# baseboard_v1.net
KiCad netlist of a schematic drawn in EAGLE
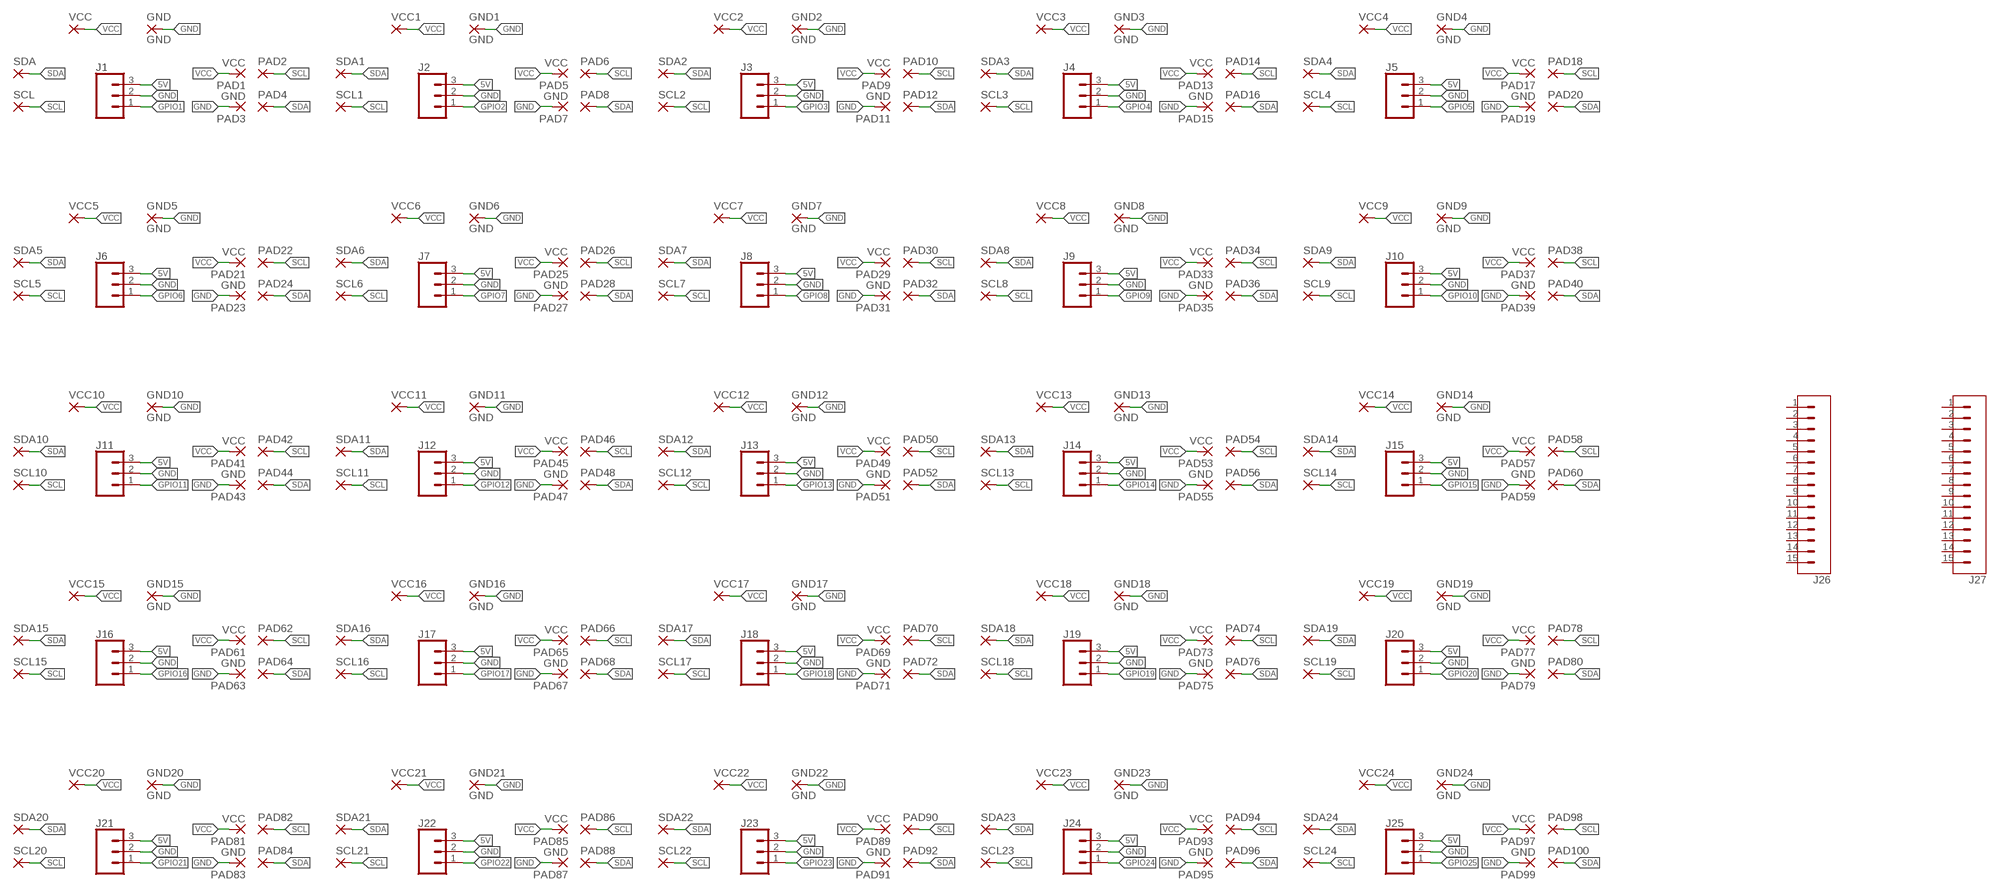
[diagram p0: schematic, sheet 1]

(export (version "E")
  (design (tool "Eeschema 10.0.6"))
  (components
    (comp (ref "GND")
      (value "GND")
      (footprint "eagle-import:2,15_1,0")
      (libsource (lib "eagle-import") (part "2,15/1,0"))
    )
    (comp (ref "GND1")
      (value "GND")
      (footprint "eagle-import:2,15_1,0")
      (libsource (lib "eagle-import") (part "2,15/1,0"))
    )
    (comp (ref "GND2")
      (value "GND")
      (footprint "eagle-import:2,15_1,0")
      (libsource (lib "eagle-import") (part "2,15/1,0"))
    )
    (comp (ref "GND3")
      (value "GND")
      (footprint "eagle-import:2,15_1,0")
      (libsource (lib "eagle-import") (part "2,15/1,0"))
    )
    (comp (ref "GND4")
      (value "GND")
      (footprint "eagle-import:2,15_1,0")
      (libsource (lib "eagle-import") (part "2,15/1,0"))
    )
    (comp (ref "GND5")
      (value "GND")
      (footprint "eagle-import:2,15_1,0")
      (libsource (lib "eagle-import") (part "2,15/1,0"))
    )
    (comp (ref "GND6")
      (value "GND")
      (footprint "eagle-import:2,15_1,0")
      (libsource (lib "eagle-import") (part "2,15/1,0"))
    )
    (comp (ref "GND7")
      (value "GND")
      (footprint "eagle-import:2,15_1,0")
      (libsource (lib "eagle-import") (part "2,15/1,0"))
    )
    (comp (ref "GND8")
      (value "GND")
      (footprint "eagle-import:2,15_1,0")
      (libsource (lib "eagle-import") (part "2,15/1,0"))
    )
    (comp (ref "GND9")
      (value "GND")
      (footprint "eagle-import:2,15_1,0")
      (libsource (lib "eagle-import") (part "2,15/1,0"))
    )
    (comp (ref "GND10")
      (value "GND")
      (footprint "eagle-import:2,15_1,0")
      (libsource (lib "eagle-import") (part "2,15/1,0"))
    )
    (comp (ref "GND11")
      (value "GND")
      (footprint "eagle-import:2,15_1,0")
      (libsource (lib "eagle-import") (part "2,15/1,0"))
    )
    (comp (ref "GND12")
      (value "GND")
      (footprint "eagle-import:2,15_1,0")
      (libsource (lib "eagle-import") (part "2,15/1,0"))
    )
    (comp (ref "GND13")
      (value "GND")
      (footprint "eagle-import:2,15_1,0")
      (libsource (lib "eagle-import") (part "2,15/1,0"))
    )
    (comp (ref "GND14")
      (value "GND")
      (footprint "eagle-import:2,15_1,0")
      (libsource (lib "eagle-import") (part "2,15/1,0"))
    )
    (comp (ref "GND15")
      (value "GND")
      (footprint "eagle-import:2,15_1,0")
      (libsource (lib "eagle-import") (part "2,15/1,0"))
    )
    (comp (ref "GND16")
      (value "GND")
      (footprint "eagle-import:2,15_1,0")
      (libsource (lib "eagle-import") (part "2,15/1,0"))
    )
    (comp (ref "GND17")
      (value "GND")
      (footprint "eagle-import:2,15_1,0")
      (libsource (lib "eagle-import") (part "2,15/1,0"))
    )
    (comp (ref "GND18")
      (value "GND")
      (footprint "eagle-import:2,15_1,0")
      (libsource (lib "eagle-import") (part "2,15/1,0"))
    )
    (comp (ref "GND19")
      (value "GND")
      (footprint "eagle-import:2,15_1,0")
      (libsource (lib "eagle-import") (part "2,15/1,0"))
    )
    (comp (ref "GND20")
      (value "GND")
      (footprint "eagle-import:2,15_1,0")
      (libsource (lib "eagle-import") (part "2,15/1,0"))
    )
    (comp (ref "GND21")
      (value "GND")
      (footprint "eagle-import:2,15_1,0")
      (libsource (lib "eagle-import") (part "2,15/1,0"))
    )
    (comp (ref "GND22")
      (value "GND")
      (footprint "eagle-import:2,15_1,0")
      (libsource (lib "eagle-import") (part "2,15/1,0"))
    )
    (comp (ref "GND23")
      (value "GND")
      (footprint "eagle-import:2,15_1,0")
      (libsource (lib "eagle-import") (part "2,15/1,0"))
    )
    (comp (ref "GND24")
      (value "GND")
      (footprint "eagle-import:2,15_1,0")
      (libsource (lib "eagle-import") (part "2,15/1,0"))
    )
    (comp (ref "J1")
      (value "CONN_03")
      (footprint "eagle-import:1X03")
      (libsource (lib "eagle-import") (part "CONN_03"))
    )
    (comp (ref "J2")
      (value "CONN_03")
      (footprint "eagle-import:1X03")
      (libsource (lib "eagle-import") (part "CONN_03"))
    )
    (comp (ref "J3")
      (value "CONN_03")
      (footprint "eagle-import:1X03")
      (libsource (lib "eagle-import") (part "CONN_03"))
    )
    (comp (ref "J4")
      (value "CONN_03")
      (footprint "eagle-import:1X03")
      (libsource (lib "eagle-import") (part "CONN_03"))
    )
    (comp (ref "J5")
      (value "CONN_03")
      (footprint "eagle-import:1X03")
      (libsource (lib "eagle-import") (part "CONN_03"))
    )
    (comp (ref "J6")
      (value "CONN_03")
      (footprint "eagle-import:1X03")
      (libsource (lib "eagle-import") (part "CONN_03"))
    )
    (comp (ref "J7")
      (value "CONN_03")
      (footprint "eagle-import:1X03")
      (libsource (lib "eagle-import") (part "CONN_03"))
    )
    (comp (ref "J8")
      (value "CONN_03")
      (footprint "eagle-import:1X03")
      (libsource (lib "eagle-import") (part "CONN_03"))
    )
    (comp (ref "J9")
      (value "CONN_03")
      (footprint "eagle-import:1X03")
      (libsource (lib "eagle-import") (part "CONN_03"))
    )
    (comp (ref "J10")
      (value "CONN_03")
      (footprint "eagle-import:1X03")
      (libsource (lib "eagle-import") (part "CONN_03"))
    )
    (comp (ref "J11")
      (value "CONN_03")
      (footprint "eagle-import:1X03")
      (libsource (lib "eagle-import") (part "CONN_03"))
    )
    (comp (ref "J12")
      (value "CONN_03")
      (footprint "eagle-import:1X03")
      (libsource (lib "eagle-import") (part "CONN_03"))
    )
    (comp (ref "J13")
      (value "CONN_03")
      (footprint "eagle-import:1X03")
      (libsource (lib "eagle-import") (part "CONN_03"))
    )
    (comp (ref "J14")
      (value "CONN_03")
      (footprint "eagle-import:1X03")
      (libsource (lib "eagle-import") (part "CONN_03"))
    )
    (comp (ref "J15")
      (value "CONN_03")
      (footprint "eagle-import:1X03")
      (libsource (lib "eagle-import") (part "CONN_03"))
    )
    (comp (ref "J16")
      (value "CONN_03")
      (footprint "eagle-import:1X03")
      (libsource (lib "eagle-import") (part "CONN_03"))
    )
    (comp (ref "J17")
      (value "CONN_03")
      (footprint "eagle-import:1X03")
      (libsource (lib "eagle-import") (part "CONN_03"))
    )
    (comp (ref "J18")
      (value "CONN_03")
      (footprint "eagle-import:1X03")
      (libsource (lib "eagle-import") (part "CONN_03"))
    )
    (comp (ref "J19")
      (value "CONN_03")
      (footprint "eagle-import:1X03")
      (libsource (lib "eagle-import") (part "CONN_03"))
    )
    (comp (ref "J20")
      (value "CONN_03")
      (footprint "eagle-import:1X03")
      (libsource (lib "eagle-import") (part "CONN_03"))
    )
    (comp (ref "J21")
      (value "CONN_03")
      (footprint "eagle-import:1X03")
      (libsource (lib "eagle-import") (part "CONN_03"))
    )
    (comp (ref "J22")
      (value "CONN_03")
      (footprint "eagle-import:1X03")
      (libsource (lib "eagle-import") (part "CONN_03"))
    )
    (comp (ref "J23")
      (value "CONN_03")
      (footprint "eagle-import:1X03")
      (libsource (lib "eagle-import") (part "CONN_03"))
    )
    (comp (ref "J24")
      (value "CONN_03")
      (footprint "eagle-import:1X03")
      (libsource (lib "eagle-import") (part "CONN_03"))
    )
    (comp (ref "J25")
      (value "CONN_03")
      (footprint "eagle-import:1X03")
      (libsource (lib "eagle-import") (part "CONN_03"))
    )
    (comp (ref "J26")
      (value "CONN_06SMD_MALE")
      (footprint "eagle-import:1X15_SMD_MALE")
      (libsource (lib "eagle-import") (part "CONN_06SMD_MALE"))
    )
    (comp (ref "J27")
      (value "CONN_06SMD_MALE")
      (footprint "eagle-import:1X15_SMD_MALE")
      (libsource (lib "eagle-import") (part "CONN_06SMD_MALE"))
    )
    (comp (ref "PAD1")
      (value "VCC")
      (footprint "eagle-import:2,15_1,0")
      (libsource (lib "eagle-import") (part "2,15/1,0"))
    )
    (comp (ref "PAD2")
      (value "2,15/1,0")
      (footprint "eagle-import:2,15_1,0")
      (libsource (lib "eagle-import") (part "2,15/1,0"))
    )
    (comp (ref "PAD3")
      (value "GND")
      (footprint "eagle-import:2,15_1,0")
      (libsource (lib "eagle-import") (part "2,15/1,0"))
    )
    (comp (ref "PAD4")
      (value "2,15/1,0")
      (footprint "eagle-import:2,15_1,0")
      (libsource (lib "eagle-import") (part "2,15/1,0"))
    )
    (comp (ref "PAD5")
      (value "VCC")
      (footprint "eagle-import:2,15_1,0")
      (libsource (lib "eagle-import") (part "2,15/1,0"))
    )
    (comp (ref "PAD6")
      (value "2,15/1,0")
      (footprint "eagle-import:2,15_1,0")
      (libsource (lib "eagle-import") (part "2,15/1,0"))
    )
    (comp (ref "PAD7")
      (value "GND")
      (footprint "eagle-import:2,15_1,0")
      (libsource (lib "eagle-import") (part "2,15/1,0"))
    )
    (comp (ref "PAD8")
      (value "2,15/1,0")
      (footprint "eagle-import:2,15_1,0")
      (libsource (lib "eagle-import") (part "2,15/1,0"))
    )
    (comp (ref "PAD9")
      (value "VCC")
      (footprint "eagle-import:2,15_1,0")
      (libsource (lib "eagle-import") (part "2,15/1,0"))
    )
    (comp (ref "PAD10")
      (value "2,15/1,0")
      (footprint "eagle-import:2,15_1,0")
      (libsource (lib "eagle-import") (part "2,15/1,0"))
    )
    (comp (ref "PAD11")
      (value "GND")
      (footprint "eagle-import:2,15_1,0")
      (libsource (lib "eagle-import") (part "2,15/1,0"))
    )
    (comp (ref "PAD12")
      (value "2,15/1,0")
      (footprint "eagle-import:2,15_1,0")
      (libsource (lib "eagle-import") (part "2,15/1,0"))
    )
    (comp (ref "PAD13")
      (value "VCC")
      (footprint "eagle-import:2,15_1,0")
      (libsource (lib "eagle-import") (part "2,15/1,0"))
    )
    (comp (ref "PAD14")
      (value "2,15/1,0")
      (footprint "eagle-import:2,15_1,0")
      (libsource (lib "eagle-import") (part "2,15/1,0"))
    )
    (comp (ref "PAD15")
      (value "GND")
      (footprint "eagle-import:2,15_1,0")
      (libsource (lib "eagle-import") (part "2,15/1,0"))
    )
    (comp (ref "PAD16")
      (value "2,15/1,0")
      (footprint "eagle-import:2,15_1,0")
      (libsource (lib "eagle-import") (part "2,15/1,0"))
    )
    (comp (ref "PAD17")
      (value "VCC")
      (footprint "eagle-import:2,15_1,0")
      (libsource (lib "eagle-import") (part "2,15/1,0"))
    )
    (comp (ref "PAD18")
      (value "2,15/1,0")
      (footprint "eagle-import:2,15_1,0")
      (libsource (lib "eagle-import") (part "2,15/1,0"))
    )
    (comp (ref "PAD19")
      (value "GND")
      (footprint "eagle-import:2,15_1,0")
      (libsource (lib "eagle-import") (part "2,15/1,0"))
    )
    (comp (ref "PAD20")
      (value "2,15/1,0")
      (footprint "eagle-import:2,15_1,0")
      (libsource (lib "eagle-import") (part "2,15/1,0"))
    )
    (comp (ref "PAD21")
      (value "VCC")
      (footprint "eagle-import:2,15_1,0")
      (libsource (lib "eagle-import") (part "2,15/1,0"))
    )
    (comp (ref "PAD22")
      (value "2,15/1,0")
      (footprint "eagle-import:2,15_1,0")
      (libsource (lib "eagle-import") (part "2,15/1,0"))
    )
    (comp (ref "PAD23")
      (value "GND")
      (footprint "eagle-import:2,15_1,0")
      (libsource (lib "eagle-import") (part "2,15/1,0"))
    )
    (comp (ref "PAD24")
      (value "2,15/1,0")
      (footprint "eagle-import:2,15_1,0")
      (libsource (lib "eagle-import") (part "2,15/1,0"))
    )
    (comp (ref "PAD25")
      (value "VCC")
      (footprint "eagle-import:2,15_1,0")
      (libsource (lib "eagle-import") (part "2,15/1,0"))
    )
    (comp (ref "PAD26")
      (value "2,15/1,0")
      (footprint "eagle-import:2,15_1,0")
      (libsource (lib "eagle-import") (part "2,15/1,0"))
    )
    (comp (ref "PAD27")
      (value "GND")
      (footprint "eagle-import:2,15_1,0")
      (libsource (lib "eagle-import") (part "2,15/1,0"))
    )
    (comp (ref "PAD28")
      (value "2,15/1,0")
      (footprint "eagle-import:2,15_1,0")
      (libsource (lib "eagle-import") (part "2,15/1,0"))
    )
    (comp (ref "PAD29")
      (value "VCC")
      (footprint "eagle-import:2,15_1,0")
      (libsource (lib "eagle-import") (part "2,15/1,0"))
    )
    (comp (ref "PAD30")
      (value "2,15/1,0")
      (footprint "eagle-import:2,15_1,0")
      (libsource (lib "eagle-import") (part "2,15/1,0"))
    )
    (comp (ref "PAD31")
      (value "GND")
      (footprint "eagle-import:2,15_1,0")
      (libsource (lib "eagle-import") (part "2,15/1,0"))
    )
    (comp (ref "PAD32")
      (value "2,15/1,0")
      (footprint "eagle-import:2,15_1,0")
      (libsource (lib "eagle-import") (part "2,15/1,0"))
    )
    (comp (ref "PAD33")
      (value "VCC")
      (footprint "eagle-import:2,15_1,0")
      (libsource (lib "eagle-import") (part "2,15/1,0"))
    )
    (comp (ref "PAD34")
      (value "2,15/1,0")
      (footprint "eagle-import:2,15_1,0")
      (libsource (lib "eagle-import") (part "2,15/1,0"))
    )
    (comp (ref "PAD35")
      (value "GND")
      (footprint "eagle-import:2,15_1,0")
      (libsource (lib "eagle-import") (part "2,15/1,0"))
    )
    (comp (ref "PAD36")
      (value "2,15/1,0")
      (footprint "eagle-import:2,15_1,0")
      (libsource (lib "eagle-import") (part "2,15/1,0"))
    )
    (comp (ref "PAD37")
      (value "VCC")
      (footprint "eagle-import:2,15_1,0")
      (libsource (lib "eagle-import") (part "2,15/1,0"))
    )
    (comp (ref "PAD38")
      (value "2,15/1,0")
      (footprint "eagle-import:2,15_1,0")
      (libsource (lib "eagle-import") (part "2,15/1,0"))
    )
    (comp (ref "PAD39")
      (value "GND")
      (footprint "eagle-import:2,15_1,0")
      (libsource (lib "eagle-import") (part "2,15/1,0"))
    )
    (comp (ref "PAD40")
      (value "2,15/1,0")
      (footprint "eagle-import:2,15_1,0")
      (libsource (lib "eagle-import") (part "2,15/1,0"))
    )
    (comp (ref "PAD41")
      (value "VCC")
      (footprint "eagle-import:2,15_1,0")
      (libsource (lib "eagle-import") (part "2,15/1,0"))
    )
    (comp (ref "PAD42")
      (value "2,15/1,0")
      (footprint "eagle-import:2,15_1,0")
      (libsource (lib "eagle-import") (part "2,15/1,0"))
    )
    (comp (ref "PAD43")
      (value "GND")
      (footprint "eagle-import:2,15_1,0")
      (libsource (lib "eagle-import") (part "2,15/1,0"))
    )
    (comp (ref "PAD44")
      (value "2,15/1,0")
      (footprint "eagle-import:2,15_1,0")
      (libsource (lib "eagle-import") (part "2,15/1,0"))
    )
    (comp (ref "PAD45")
      (value "VCC")
      (footprint "eagle-import:2,15_1,0")
      (libsource (lib "eagle-import") (part "2,15/1,0"))
    )
    (comp (ref "PAD46")
      (value "2,15/1,0")
      (footprint "eagle-import:2,15_1,0")
      (libsource (lib "eagle-import") (part "2,15/1,0"))
    )
    (comp (ref "PAD47")
      (value "GND")
      (footprint "eagle-import:2,15_1,0")
      (libsource (lib "eagle-import") (part "2,15/1,0"))
    )
    (comp (ref "PAD48")
      (value "2,15/1,0")
      (footprint "eagle-import:2,15_1,0")
      (libsource (lib "eagle-import") (part "2,15/1,0"))
    )
    (comp (ref "PAD49")
      (value "VCC")
      (footprint "eagle-import:2,15_1,0")
      (libsource (lib "eagle-import") (part "2,15/1,0"))
    )
    (comp (ref "PAD50")
      (value "2,15/1,0")
      (footprint "eagle-import:2,15_1,0")
      (libsource (lib "eagle-import") (part "2,15/1,0"))
    )
    (comp (ref "PAD51")
      (value "GND")
      (footprint "eagle-import:2,15_1,0")
      (libsource (lib "eagle-import") (part "2,15/1,0"))
    )
    (comp (ref "PAD52")
      (value "2,15/1,0")
      (footprint "eagle-import:2,15_1,0")
      (libsource (lib "eagle-import") (part "2,15/1,0"))
    )
    (comp (ref "PAD53")
      (value "VCC")
      (footprint "eagle-import:2,15_1,0")
      (libsource (lib "eagle-import") (part "2,15/1,0"))
    )
    (comp (ref "PAD54")
      (value "2,15/1,0")
      (footprint "eagle-import:2,15_1,0")
      (libsource (lib "eagle-import") (part "2,15/1,0"))
    )
    (comp (ref "PAD55")
      (value "GND")
      (footprint "eagle-import:2,15_1,0")
      (libsource (lib "eagle-import") (part "2,15/1,0"))
    )
    (comp (ref "PAD56")
      (value "2,15/1,0")
      (footprint "eagle-import:2,15_1,0")
      (libsource (lib "eagle-import") (part "2,15/1,0"))
    )
    (comp (ref "PAD57")
      (value "VCC")
      (footprint "eagle-import:2,15_1,0")
      (libsource (lib "eagle-import") (part "2,15/1,0"))
    )
    (comp (ref "PAD58")
      (value "2,15/1,0")
      (footprint "eagle-import:2,15_1,0")
      (libsource (lib "eagle-import") (part "2,15/1,0"))
    )
    (comp (ref "PAD59")
      (value "GND")
      (footprint "eagle-import:2,15_1,0")
      (libsource (lib "eagle-import") (part "2,15/1,0"))
    )
    (comp (ref "PAD60")
      (value "2,15/1,0")
      (footprint "eagle-import:2,15_1,0")
      (libsource (lib "eagle-import") (part "2,15/1,0"))
    )
    (comp (ref "PAD61")
      (value "VCC")
      (footprint "eagle-import:2,15_1,0")
      (libsource (lib "eagle-import") (part "2,15/1,0"))
    )
    (comp (ref "PAD62")
      (value "2,15/1,0")
      (footprint "eagle-import:2,15_1,0")
      (libsource (lib "eagle-import") (part "2,15/1,0"))
    )
    (comp (ref "PAD63")
      (value "GND")
      (footprint "eagle-import:2,15_1,0")
      (libsource (lib "eagle-import") (part "2,15/1,0"))
    )
    (comp (ref "PAD64")
      (value "2,15/1,0")
      (footprint "eagle-import:2,15_1,0")
      (libsource (lib "eagle-import") (part "2,15/1,0"))
    )
    (comp (ref "PAD65")
      (value "VCC")
      (footprint "eagle-import:2,15_1,0")
      (libsource (lib "eagle-import") (part "2,15/1,0"))
    )
    (comp (ref "PAD66")
      (value "2,15/1,0")
      (footprint "eagle-import:2,15_1,0")
      (libsource (lib "eagle-import") (part "2,15/1,0"))
    )
    (comp (ref "PAD67")
      (value "GND")
      (footprint "eagle-import:2,15_1,0")
      (libsource (lib "eagle-import") (part "2,15/1,0"))
    )
    (comp (ref "PAD68")
      (value "2,15/1,0")
      (footprint "eagle-import:2,15_1,0")
      (libsource (lib "eagle-import") (part "2,15/1,0"))
    )
    (comp (ref "PAD69")
      (value "VCC")
      (footprint "eagle-import:2,15_1,0")
      (libsource (lib "eagle-import") (part "2,15/1,0"))
    )
    (comp (ref "PAD70")
      (value "2,15/1,0")
      (footprint "eagle-import:2,15_1,0")
      (libsource (lib "eagle-import") (part "2,15/1,0"))
    )
    (comp (ref "PAD71")
      (value "GND")
      (footprint "eagle-import:2,15_1,0")
      (libsource (lib "eagle-import") (part "2,15/1,0"))
    )
    (comp (ref "PAD72")
      (value "2,15/1,0")
      (footprint "eagle-import:2,15_1,0")
      (libsource (lib "eagle-import") (part "2,15/1,0"))
    )
    (comp (ref "PAD73")
      (value "VCC")
      (footprint "eagle-import:2,15_1,0")
      (libsource (lib "eagle-import") (part "2,15/1,0"))
    )
    (comp (ref "PAD74")
      (value "2,15/1,0")
      (footprint "eagle-import:2,15_1,0")
      (libsource (lib "eagle-import") (part "2,15/1,0"))
    )
    (comp (ref "PAD75")
      (value "GND")
      (footprint "eagle-import:2,15_1,0")
      (libsource (lib "eagle-import") (part "2,15/1,0"))
    )
    (comp (ref "PAD76")
      (value "2,15/1,0")
      (footprint "eagle-import:2,15_1,0")
      (libsource (lib "eagle-import") (part "2,15/1,0"))
    )
    (comp (ref "PAD77")
      (value "VCC")
      (footprint "eagle-import:2,15_1,0")
      (libsource (lib "eagle-import") (part "2,15/1,0"))
    )
    (comp (ref "PAD78")
      (value "2,15/1,0")
      (footprint "eagle-import:2,15_1,0")
      (libsource (lib "eagle-import") (part "2,15/1,0"))
    )
    (comp (ref "PAD79")
      (value "GND")
      (footprint "eagle-import:2,15_1,0")
      (libsource (lib "eagle-import") (part "2,15/1,0"))
    )
    (comp (ref "PAD80")
      (value "2,15/1,0")
      (footprint "eagle-import:2,15_1,0")
      (libsource (lib "eagle-import") (part "2,15/1,0"))
    )
    (comp (ref "PAD81")
      (value "VCC")
      (footprint "eagle-import:2,15_1,0")
      (libsource (lib "eagle-import") (part "2,15/1,0"))
    )
    (comp (ref "PAD82")
      (value "2,15/1,0")
      (footprint "eagle-import:2,15_1,0")
      (libsource (lib "eagle-import") (part "2,15/1,0"))
    )
    (comp (ref "PAD83")
      (value "GND")
      (footprint "eagle-import:2,15_1,0")
      (libsource (lib "eagle-import") (part "2,15/1,0"))
    )
    (comp (ref "PAD84")
      (value "2,15/1,0")
      (footprint "eagle-import:2,15_1,0")
      (libsource (lib "eagle-import") (part "2,15/1,0"))
    )
    (comp (ref "PAD85")
      (value "VCC")
      (footprint "eagle-import:2,15_1,0")
      (libsource (lib "eagle-import") (part "2,15/1,0"))
    )
    (comp (ref "PAD86")
      (value "2,15/1,0")
      (footprint "eagle-import:2,15_1,0")
      (libsource (lib "eagle-import") (part "2,15/1,0"))
    )
    (comp (ref "PAD87")
      (value "GND")
      (footprint "eagle-import:2,15_1,0")
      (libsource (lib "eagle-import") (part "2,15/1,0"))
    )
    (comp (ref "PAD88")
      (value "2,15/1,0")
      (footprint "eagle-import:2,15_1,0")
      (libsource (lib "eagle-import") (part "2,15/1,0"))
    )
    (comp (ref "PAD89")
      (value "VCC")
      (footprint "eagle-import:2,15_1,0")
      (libsource (lib "eagle-import") (part "2,15/1,0"))
    )
    (comp (ref "PAD90")
      (value "2,15/1,0")
      (footprint "eagle-import:2,15_1,0")
      (libsource (lib "eagle-import") (part "2,15/1,0"))
    )
    (comp (ref "PAD91")
      (value "GND")
      (footprint "eagle-import:2,15_1,0")
      (libsource (lib "eagle-import") (part "2,15/1,0"))
    )
    (comp (ref "PAD92")
      (value "2,15/1,0")
      (footprint "eagle-import:2,15_1,0")
      (libsource (lib "eagle-import") (part "2,15/1,0"))
    )
    (comp (ref "PAD93")
      (value "VCC")
      (footprint "eagle-import:2,15_1,0")
      (libsource (lib "eagle-import") (part "2,15/1,0"))
    )
    (comp (ref "PAD94")
      (value "2,15/1,0")
      (footprint "eagle-import:2,15_1,0")
      (libsource (lib "eagle-import") (part "2,15/1,0"))
    )
    (comp (ref "PAD95")
      (value "GND")
      (footprint "eagle-import:2,15_1,0")
      (libsource (lib "eagle-import") (part "2,15/1,0"))
    )
    (comp (ref "PAD96")
      (value "2,15/1,0")
      (footprint "eagle-import:2,15_1,0")
      (libsource (lib "eagle-import") (part "2,15/1,0"))
    )
    (comp (ref "PAD97")
      (value "VCC")
      (footprint "eagle-import:2,15_1,0")
      (libsource (lib "eagle-import") (part "2,15/1,0"))
    )
    (comp (ref "PAD98")
      (value "2,15/1,0")
      (footprint "eagle-import:2,15_1,0")
      (libsource (lib "eagle-import") (part "2,15/1,0"))
    )
    (comp (ref "PAD99")
      (value "GND")
      (footprint "eagle-import:2,15_1,0")
      (libsource (lib "eagle-import") (part "2,15/1,0"))
    )
    (comp (ref "PAD100")
      (value "2,15/1,0")
      (footprint "eagle-import:2,15_1,0")
      (libsource (lib "eagle-import") (part "2,15/1,0"))
    )
    (comp (ref "SCL")
      (value "2,15/1,0")
      (footprint "eagle-import:2,15_1,0")
      (libsource (lib "eagle-import") (part "2,15/1,0"))
    )
    (comp (ref "SCL1")
      (value "2,15/1,0")
      (footprint "eagle-import:2,15_1,0")
      (libsource (lib "eagle-import") (part "2,15/1,0"))
    )
    (comp (ref "SCL2")
      (value "2,15/1,0")
      (footprint "eagle-import:2,15_1,0")
      (libsource (lib "eagle-import") (part "2,15/1,0"))
    )
    (comp (ref "SCL3")
      (value "2,15/1,0")
      (footprint "eagle-import:2,15_1,0")
      (libsource (lib "eagle-import") (part "2,15/1,0"))
    )
    (comp (ref "SCL4")
      (value "2,15/1,0")
      (footprint "eagle-import:2,15_1,0")
      (libsource (lib "eagle-import") (part "2,15/1,0"))
    )
    (comp (ref "SCL5")
      (value "2,15/1,0")
      (footprint "eagle-import:2,15_1,0")
      (libsource (lib "eagle-import") (part "2,15/1,0"))
    )
    (comp (ref "SCL6")
      (value "2,15/1,0")
      (footprint "eagle-import:2,15_1,0")
      (libsource (lib "eagle-import") (part "2,15/1,0"))
    )
    (comp (ref "SCL7")
      (value "2,15/1,0")
      (footprint "eagle-import:2,15_1,0")
      (libsource (lib "eagle-import") (part "2,15/1,0"))
    )
    (comp (ref "SCL8")
      (value "2,15/1,0")
      (footprint "eagle-import:2,15_1,0")
      (libsource (lib "eagle-import") (part "2,15/1,0"))
    )
    (comp (ref "SCL9")
      (value "2,15/1,0")
      (footprint "eagle-import:2,15_1,0")
      (libsource (lib "eagle-import") (part "2,15/1,0"))
    )
    (comp (ref "SCL10")
      (value "2,15/1,0")
      (footprint "eagle-import:2,15_1,0")
      (libsource (lib "eagle-import") (part "2,15/1,0"))
    )
    (comp (ref "SCL11")
      (value "2,15/1,0")
      (footprint "eagle-import:2,15_1,0")
      (libsource (lib "eagle-import") (part "2,15/1,0"))
    )
    (comp (ref "SCL12")
      (value "2,15/1,0")
      (footprint "eagle-import:2,15_1,0")
      (libsource (lib "eagle-import") (part "2,15/1,0"))
    )
    (comp (ref "SCL13")
      (value "2,15/1,0")
      (footprint "eagle-import:2,15_1,0")
      (libsource (lib "eagle-import") (part "2,15/1,0"))
    )
    (comp (ref "SCL14")
      (value "2,15/1,0")
      (footprint "eagle-import:2,15_1,0")
      (libsource (lib "eagle-import") (part "2,15/1,0"))
    )
    (comp (ref "SCL15")
      (value "2,15/1,0")
      (footprint "eagle-import:2,15_1,0")
      (libsource (lib "eagle-import") (part "2,15/1,0"))
    )
    (comp (ref "SCL16")
      (value "2,15/1,0")
      (footprint "eagle-import:2,15_1,0")
      (libsource (lib "eagle-import") (part "2,15/1,0"))
    )
    (comp (ref "SCL17")
      (value "2,15/1,0")
      (footprint "eagle-import:2,15_1,0")
      (libsource (lib "eagle-import") (part "2,15/1,0"))
    )
    (comp (ref "SCL18")
      (value "2,15/1,0")
      (footprint "eagle-import:2,15_1,0")
      (libsource (lib "eagle-import") (part "2,15/1,0"))
    )
    (comp (ref "SCL19")
      (value "2,15/1,0")
      (footprint "eagle-import:2,15_1,0")
      (libsource (lib "eagle-import") (part "2,15/1,0"))
    )
    (comp (ref "SCL20")
      (value "2,15/1,0")
      (footprint "eagle-import:2,15_1,0")
      (libsource (lib "eagle-import") (part "2,15/1,0"))
    )
    (comp (ref "SCL21")
      (value "2,15/1,0")
      (footprint "eagle-import:2,15_1,0")
      (libsource (lib "eagle-import") (part "2,15/1,0"))
    )
    (comp (ref "SCL22")
      (value "2,15/1,0")
      (footprint "eagle-import:2,15_1,0")
      (libsource (lib "eagle-import") (part "2,15/1,0"))
    )
    (comp (ref "SCL23")
      (value "2,15/1,0")
      (footprint "eagle-import:2,15_1,0")
      (libsource (lib "eagle-import") (part "2,15/1,0"))
    )
    (comp (ref "SCL24")
      (value "2,15/1,0")
      (footprint "eagle-import:2,15_1,0")
      (libsource (lib "eagle-import") (part "2,15/1,0"))
    )
    (comp (ref "SDA")
      (value "2,15/1,0")
      (footprint "eagle-import:2,15_1,0")
      (libsource (lib "eagle-import") (part "2,15/1,0"))
    )
    (comp (ref "SDA1")
      (value "2,15/1,0")
      (footprint "eagle-import:2,15_1,0")
      (libsource (lib "eagle-import") (part "2,15/1,0"))
    )
    (comp (ref "SDA2")
      (value "2,15/1,0")
      (footprint "eagle-import:2,15_1,0")
      (libsource (lib "eagle-import") (part "2,15/1,0"))
    )
    (comp (ref "SDA3")
      (value "2,15/1,0")
      (footprint "eagle-import:2,15_1,0")
      (libsource (lib "eagle-import") (part "2,15/1,0"))
    )
    (comp (ref "SDA4")
      (value "2,15/1,0")
      (footprint "eagle-import:2,15_1,0")
      (libsource (lib "eagle-import") (part "2,15/1,0"))
    )
    (comp (ref "SDA5")
      (value "2,15/1,0")
      (footprint "eagle-import:2,15_1,0")
      (libsource (lib "eagle-import") (part "2,15/1,0"))
    )
    (comp (ref "SDA6")
      (value "2,15/1,0")
      (footprint "eagle-import:2,15_1,0")
      (libsource (lib "eagle-import") (part "2,15/1,0"))
    )
    (comp (ref "SDA7")
      (value "2,15/1,0")
      (footprint "eagle-import:2,15_1,0")
      (libsource (lib "eagle-import") (part "2,15/1,0"))
    )
    (comp (ref "SDA8")
      (value "2,15/1,0")
      (footprint "eagle-import:2,15_1,0")
      (libsource (lib "eagle-import") (part "2,15/1,0"))
    )
    (comp (ref "SDA9")
      (value "2,15/1,0")
      (footprint "eagle-import:2,15_1,0")
      (libsource (lib "eagle-import") (part "2,15/1,0"))
    )
    (comp (ref "SDA10")
      (value "2,15/1,0")
      (footprint "eagle-import:2,15_1,0")
      (libsource (lib "eagle-import") (part "2,15/1,0"))
    )
    (comp (ref "SDA11")
      (value "2,15/1,0")
      (footprint "eagle-import:2,15_1,0")
      (libsource (lib "eagle-import") (part "2,15/1,0"))
    )
    (comp (ref "SDA12")
      (value "2,15/1,0")
      (footprint "eagle-import:2,15_1,0")
      (libsource (lib "eagle-import") (part "2,15/1,0"))
    )
    (comp (ref "SDA13")
      (value "2,15/1,0")
      (footprint "eagle-import:2,15_1,0")
      (libsource (lib "eagle-import") (part "2,15/1,0"))
    )
    (comp (ref "SDA14")
      (value "2,15/1,0")
      (footprint "eagle-import:2,15_1,0")
      (libsource (lib "eagle-import") (part "2,15/1,0"))
    )
    (comp (ref "SDA15")
      (value "2,15/1,0")
      (footprint "eagle-import:2,15_1,0")
      (libsource (lib "eagle-import") (part "2,15/1,0"))
    )
    (comp (ref "SDA16")
      (value "2,15/1,0")
      (footprint "eagle-import:2,15_1,0")
      (libsource (lib "eagle-import") (part "2,15/1,0"))
    )
    (comp (ref "SDA17")
      (value "2,15/1,0")
      (footprint "eagle-import:2,15_1,0")
      (libsource (lib "eagle-import") (part "2,15/1,0"))
    )
    (comp (ref "SDA18")
      (value "2,15/1,0")
      (footprint "eagle-import:2,15_1,0")
      (libsource (lib "eagle-import") (part "2,15/1,0"))
    )
    (comp (ref "SDA19")
      (value "2,15/1,0")
      (footprint "eagle-import:2,15_1,0")
      (libsource (lib "eagle-import") (part "2,15/1,0"))
    )
    (comp (ref "SDA20")
      (value "2,15/1,0")
      (footprint "eagle-import:2,15_1,0")
      (libsource (lib "eagle-import") (part "2,15/1,0"))
    )
    (comp (ref "SDA21")
      (value "2,15/1,0")
      (footprint "eagle-import:2,15_1,0")
      (libsource (lib "eagle-import") (part "2,15/1,0"))
    )
    (comp (ref "SDA22")
      (value "2,15/1,0")
      (footprint "eagle-import:2,15_1,0")
      (libsource (lib "eagle-import") (part "2,15/1,0"))
    )
    (comp (ref "SDA23")
      (value "2,15/1,0")
      (footprint "eagle-import:2,15_1,0")
      (libsource (lib "eagle-import") (part "2,15/1,0"))
    )
    (comp (ref "SDA24")
      (value "2,15/1,0")
      (footprint "eagle-import:2,15_1,0")
      (libsource (lib "eagle-import") (part "2,15/1,0"))
    )
    (comp (ref "VCC")
      (value "2,15/1,0")
      (footprint "eagle-import:2,15_1,0")
      (libsource (lib "eagle-import") (part "2,15/1,0"))
    )
    (comp (ref "VCC1")
      (value "2,15/1,0")
      (footprint "eagle-import:2,15_1,0")
      (libsource (lib "eagle-import") (part "2,15/1,0"))
    )
    (comp (ref "VCC2")
      (value "2,15/1,0")
      (footprint "eagle-import:2,15_1,0")
      (libsource (lib "eagle-import") (part "2,15/1,0"))
    )
    (comp (ref "VCC3")
      (value "2,15/1,0")
      (footprint "eagle-import:2,15_1,0")
      (libsource (lib "eagle-import") (part "2,15/1,0"))
    )
    (comp (ref "VCC4")
      (value "2,15/1,0")
      (footprint "eagle-import:2,15_1,0")
      (libsource (lib "eagle-import") (part "2,15/1,0"))
    )
    (comp (ref "VCC5")
      (value "2,15/1,0")
      (footprint "eagle-import:2,15_1,0")
      (libsource (lib "eagle-import") (part "2,15/1,0"))
    )
    (comp (ref "VCC6")
      (value "2,15/1,0")
      (footprint "eagle-import:2,15_1,0")
      (libsource (lib "eagle-import") (part "2,15/1,0"))
    )
    (comp (ref "VCC7")
      (value "2,15/1,0")
      (footprint "eagle-import:2,15_1,0")
      (libsource (lib "eagle-import") (part "2,15/1,0"))
    )
    (comp (ref "VCC8")
      (value "2,15/1,0")
      (footprint "eagle-import:2,15_1,0")
      (libsource (lib "eagle-import") (part "2,15/1,0"))
    )
    (comp (ref "VCC9")
      (value "2,15/1,0")
      (footprint "eagle-import:2,15_1,0")
      (libsource (lib "eagle-import") (part "2,15/1,0"))
    )
    (comp (ref "VCC10")
      (value "2,15/1,0")
      (footprint "eagle-import:2,15_1,0")
      (libsource (lib "eagle-import") (part "2,15/1,0"))
    )
    (comp (ref "VCC11")
      (value "2,15/1,0")
      (footprint "eagle-import:2,15_1,0")
      (libsource (lib "eagle-import") (part "2,15/1,0"))
    )
    (comp (ref "VCC12")
      (value "2,15/1,0")
      (footprint "eagle-import:2,15_1,0")
      (libsource (lib "eagle-import") (part "2,15/1,0"))
    )
    (comp (ref "VCC13")
      (value "2,15/1,0")
      (footprint "eagle-import:2,15_1,0")
      (libsource (lib "eagle-import") (part "2,15/1,0"))
    )
    (comp (ref "VCC14")
      (value "2,15/1,0")
      (footprint "eagle-import:2,15_1,0")
      (libsource (lib "eagle-import") (part "2,15/1,0"))
    )
    (comp (ref "VCC15")
      (value "2,15/1,0")
      (footprint "eagle-import:2,15_1,0")
      (libsource (lib "eagle-import") (part "2,15/1,0"))
    )
    (comp (ref "VCC16")
      (value "2,15/1,0")
      (footprint "eagle-import:2,15_1,0")
      (libsource (lib "eagle-import") (part "2,15/1,0"))
    )
    (comp (ref "VCC17")
      (value "2,15/1,0")
      (footprint "eagle-import:2,15_1,0")
      (libsource (lib "eagle-import") (part "2,15/1,0"))
    )
    (comp (ref "VCC18")
      (value "2,15/1,0")
      (footprint "eagle-import:2,15_1,0")
      (libsource (lib "eagle-import") (part "2,15/1,0"))
    )
    (comp (ref "VCC19")
      (value "2,15/1,0")
      (footprint "eagle-import:2,15_1,0")
      (libsource (lib "eagle-import") (part "2,15/1,0"))
    )
    (comp (ref "VCC20")
      (value "2,15/1,0")
      (footprint "eagle-import:2,15_1,0")
      (libsource (lib "eagle-import") (part "2,15/1,0"))
    )
    (comp (ref "VCC21")
      (value "2,15/1,0")
      (footprint "eagle-import:2,15_1,0")
      (libsource (lib "eagle-import") (part "2,15/1,0"))
    )
    (comp (ref "VCC22")
      (value "2,15/1,0")
      (footprint "eagle-import:2,15_1,0")
      (libsource (lib "eagle-import") (part "2,15/1,0"))
    )
    (comp (ref "VCC23")
      (value "2,15/1,0")
      (footprint "eagle-import:2,15_1,0")
      (libsource (lib "eagle-import") (part "2,15/1,0"))
    )
    (comp (ref "VCC24")
      (value "2,15/1,0")
      (footprint "eagle-import:2,15_1,0")
      (libsource (lib "eagle-import") (part "2,15/1,0"))
    )
  )
  (nets
    (net (code "1") (name "5V") (class "Default")
      (node (ref "J1") (pin "3") (pinfunction "3_3") (pintype "passive"))
      (node (ref "J10") (pin "3") (pinfunction "3_3") (pintype "passive"))
      (node (ref "J11") (pin "3") (pinfunction "3_3") (pintype "passive"))
      (node (ref "J12") (pin "3") (pinfunction "3_3") (pintype "passive"))
      (node (ref "J13") (pin "3") (pinfunction "3_3") (pintype "passive"))
      (node (ref "J14") (pin "3") (pinfunction "3_3") (pintype "passive"))
      (node (ref "J15") (pin "3") (pinfunction "3_3") (pintype "passive"))
      (node (ref "J16") (pin "3") (pinfunction "3_3") (pintype "passive"))
      (node (ref "J17") (pin "3") (pinfunction "3_3") (pintype "passive"))
      (node (ref "J18") (pin "3") (pinfunction "3_3") (pintype "passive"))
      (node (ref "J19") (pin "3") (pinfunction "3_3") (pintype "passive"))
      (node (ref "J2") (pin "3") (pinfunction "3_3") (pintype "passive"))
      (node (ref "J20") (pin "3") (pinfunction "3_3") (pintype "passive"))
      (node (ref "J21") (pin "3") (pinfunction "3_3") (pintype "passive"))
      (node (ref "J22") (pin "3") (pinfunction "3_3") (pintype "passive"))
      (node (ref "J23") (pin "3") (pinfunction "3_3") (pintype "passive"))
      (node (ref "J24") (pin "3") (pinfunction "3_3") (pintype "passive"))
      (node (ref "J25") (pin "3") (pinfunction "3_3") (pintype "passive"))
      (node (ref "J3") (pin "3") (pinfunction "3_3") (pintype "passive"))
      (node (ref "J4") (pin "3") (pinfunction "3_3") (pintype "passive"))
      (node (ref "J5") (pin "3") (pinfunction "3_3") (pintype "passive"))
      (node (ref "J6") (pin "3") (pinfunction "3_3") (pintype "passive"))
      (node (ref "J7") (pin "3") (pinfunction "3_3") (pintype "passive"))
      (node (ref "J8") (pin "3") (pinfunction "3_3") (pintype "passive"))
      (node (ref "J9") (pin "3") (pinfunction "3_3") (pintype "passive"))
    )
    (net (code "2") (name "GND") (class "Default")
      (node (ref "GND") (pin "1") (pinfunction "P_1") (pintype "passive"))
      (node (ref "GND1") (pin "1") (pinfunction "P_1") (pintype "passive"))
      (node (ref "GND10") (pin "1") (pinfunction "P_1") (pintype "passive"))
      (node (ref "GND11") (pin "1") (pinfunction "P_1") (pintype "passive"))
      (node (ref "GND12") (pin "1") (pinfunction "P_1") (pintype "passive"))
      (node (ref "GND13") (pin "1") (pinfunction "P_1") (pintype "passive"))
      (node (ref "GND14") (pin "1") (pinfunction "P_1") (pintype "passive"))
      (node (ref "GND15") (pin "1") (pinfunction "P_1") (pintype "passive"))
      (node (ref "GND16") (pin "1") (pinfunction "P_1") (pintype "passive"))
      (node (ref "GND17") (pin "1") (pinfunction "P_1") (pintype "passive"))
      (node (ref "GND18") (pin "1") (pinfunction "P_1") (pintype "passive"))
      (node (ref "GND19") (pin "1") (pinfunction "P_1") (pintype "passive"))
      (node (ref "GND2") (pin "1") (pinfunction "P_1") (pintype "passive"))
      (node (ref "GND20") (pin "1") (pinfunction "P_1") (pintype "passive"))
      (node (ref "GND21") (pin "1") (pinfunction "P_1") (pintype "passive"))
      (node (ref "GND22") (pin "1") (pinfunction "P_1") (pintype "passive"))
      (node (ref "GND23") (pin "1") (pinfunction "P_1") (pintype "passive"))
      (node (ref "GND24") (pin "1") (pinfunction "P_1") (pintype "passive"))
      (node (ref "GND3") (pin "1") (pinfunction "P_1") (pintype "passive"))
      (node (ref "GND4") (pin "1") (pinfunction "P_1") (pintype "passive"))
      (node (ref "GND5") (pin "1") (pinfunction "P_1") (pintype "passive"))
      (node (ref "GND6") (pin "1") (pinfunction "P_1") (pintype "passive"))
      (node (ref "GND7") (pin "1") (pinfunction "P_1") (pintype "passive"))
      (node (ref "GND8") (pin "1") (pinfunction "P_1") (pintype "passive"))
      (node (ref "GND9") (pin "1") (pinfunction "P_1") (pintype "passive"))
      (node (ref "J1") (pin "2") (pinfunction "2_2") (pintype "passive"))
      (node (ref "J10") (pin "2") (pinfunction "2_2") (pintype "passive"))
      (node (ref "J11") (pin "2") (pinfunction "2_2") (pintype "passive"))
      (node (ref "J12") (pin "2") (pinfunction "2_2") (pintype "passive"))
      (node (ref "J13") (pin "2") (pinfunction "2_2") (pintype "passive"))
      (node (ref "J14") (pin "2") (pinfunction "2_2") (pintype "passive"))
      (node (ref "J15") (pin "2") (pinfunction "2_2") (pintype "passive"))
      (node (ref "J16") (pin "2") (pinfunction "2_2") (pintype "passive"))
      (node (ref "J17") (pin "2") (pinfunction "2_2") (pintype "passive"))
      (node (ref "J18") (pin "2") (pinfunction "2_2") (pintype "passive"))
      (node (ref "J19") (pin "2") (pinfunction "2_2") (pintype "passive"))
      (node (ref "J2") (pin "2") (pinfunction "2_2") (pintype "passive"))
      (node (ref "J20") (pin "2") (pinfunction "2_2") (pintype "passive"))
      (node (ref "J21") (pin "2") (pinfunction "2_2") (pintype "passive"))
      (node (ref "J22") (pin "2") (pinfunction "2_2") (pintype "passive"))
      (node (ref "J23") (pin "2") (pinfunction "2_2") (pintype "passive"))
      (node (ref "J24") (pin "2") (pinfunction "2_2") (pintype "passive"))
      (node (ref "J25") (pin "2") (pinfunction "2_2") (pintype "passive"))
      (node (ref "J3") (pin "2") (pinfunction "2_2") (pintype "passive"))
      (node (ref "J4") (pin "2") (pinfunction "2_2") (pintype "passive"))
      (node (ref "J5") (pin "2") (pinfunction "2_2") (pintype "passive"))
      (node (ref "J6") (pin "2") (pinfunction "2_2") (pintype "passive"))
      (node (ref "J7") (pin "2") (pinfunction "2_2") (pintype "passive"))
      (node (ref "J8") (pin "2") (pinfunction "2_2") (pintype "passive"))
      (node (ref "J9") (pin "2") (pinfunction "2_2") (pintype "passive"))
      (node (ref "PAD11") (pin "1") (pinfunction "P_1") (pintype "passive"))
      (node (ref "PAD15") (pin "1") (pinfunction "P_1") (pintype "passive"))
      (node (ref "PAD19") (pin "1") (pinfunction "P_1") (pintype "passive"))
      (node (ref "PAD23") (pin "1") (pinfunction "P_1") (pintype "passive"))
      (node (ref "PAD27") (pin "1") (pinfunction "P_1") (pintype "passive"))
      (node (ref "PAD3") (pin "1") (pinfunction "P_1") (pintype "passive"))
      (node (ref "PAD31") (pin "1") (pinfunction "P_1") (pintype "passive"))
      (node (ref "PAD35") (pin "1") (pinfunction "P_1") (pintype "passive"))
      (node (ref "PAD39") (pin "1") (pinfunction "P_1") (pintype "passive"))
      (node (ref "PAD43") (pin "1") (pinfunction "P_1") (pintype "passive"))
      (node (ref "PAD47") (pin "1") (pinfunction "P_1") (pintype "passive"))
      (node (ref "PAD51") (pin "1") (pinfunction "P_1") (pintype "passive"))
      (node (ref "PAD55") (pin "1") (pinfunction "P_1") (pintype "passive"))
      (node (ref "PAD59") (pin "1") (pinfunction "P_1") (pintype "passive"))
      (node (ref "PAD63") (pin "1") (pinfunction "P_1") (pintype "passive"))
      (node (ref "PAD67") (pin "1") (pinfunction "P_1") (pintype "passive"))
      (node (ref "PAD7") (pin "1") (pinfunction "P_1") (pintype "passive"))
      (node (ref "PAD71") (pin "1") (pinfunction "P_1") (pintype "passive"))
      (node (ref "PAD75") (pin "1") (pinfunction "P_1") (pintype "passive"))
      (node (ref "PAD79") (pin "1") (pinfunction "P_1") (pintype "passive"))
      (node (ref "PAD83") (pin "1") (pinfunction "P_1") (pintype "passive"))
      (node (ref "PAD87") (pin "1") (pinfunction "P_1") (pintype "passive"))
      (node (ref "PAD91") (pin "1") (pinfunction "P_1") (pintype "passive"))
      (node (ref "PAD95") (pin "1") (pinfunction "P_1") (pintype "passive"))
      (node (ref "PAD99") (pin "1") (pinfunction "P_1") (pintype "passive"))
    )
    (net (code "3") (name "GPIO1") (class "Default")
      (node (ref "J1") (pin "1") (pinfunction "1_1") (pintype "passive"))
    )
    (net (code "4") (name "GPIO2") (class "Default")
      (node (ref "J2") (pin "1") (pinfunction "1_1") (pintype "passive"))
    )
    (net (code "5") (name "GPIO3") (class "Default")
      (node (ref "J3") (pin "1") (pinfunction "1_1") (pintype "passive"))
    )
    (net (code "6") (name "GPIO4") (class "Default")
      (node (ref "J4") (pin "1") (pinfunction "1_1") (pintype "passive"))
    )
    (net (code "7") (name "GPIO5") (class "Default")
      (node (ref "J5") (pin "1") (pinfunction "1_1") (pintype "passive"))
    )
    (net (code "8") (name "GPIO6") (class "Default")
      (node (ref "J6") (pin "1") (pinfunction "1_1") (pintype "passive"))
    )
    (net (code "9") (name "GPIO7") (class "Default")
      (node (ref "J7") (pin "1") (pinfunction "1_1") (pintype "passive"))
    )
    (net (code "10") (name "GPIO8") (class "Default")
      (node (ref "J8") (pin "1") (pinfunction "1_1") (pintype "passive"))
    )
    (net (code "11") (name "GPIO9") (class "Default")
      (node (ref "J9") (pin "1") (pinfunction "1_1") (pintype "passive"))
    )
    (net (code "12") (name "GPIO10") (class "Default")
      (node (ref "J10") (pin "1") (pinfunction "1_1") (pintype "passive"))
    )
    (net (code "13") (name "GPIO11") (class "Default")
      (node (ref "J11") (pin "1") (pinfunction "1_1") (pintype "passive"))
    )
    (net (code "14") (name "GPIO12") (class "Default")
      (node (ref "J12") (pin "1") (pinfunction "1_1") (pintype "passive"))
    )
    (net (code "15") (name "GPIO13") (class "Default")
      (node (ref "J13") (pin "1") (pinfunction "1_1") (pintype "passive"))
    )
    (net (code "16") (name "GPIO14") (class "Default")
      (node (ref "J14") (pin "1") (pinfunction "1_1") (pintype "passive"))
    )
    (net (code "17") (name "GPIO15") (class "Default")
      (node (ref "J15") (pin "1") (pinfunction "1_1") (pintype "passive"))
    )
    (net (code "18") (name "GPIO16") (class "Default")
      (node (ref "J16") (pin "1") (pinfunction "1_1") (pintype "passive"))
    )
    (net (code "19") (name "GPIO17") (class "Default")
      (node (ref "J17") (pin "1") (pinfunction "1_1") (pintype "passive"))
    )
    (net (code "20") (name "GPIO18") (class "Default")
      (node (ref "J18") (pin "1") (pinfunction "1_1") (pintype "passive"))
    )
    (net (code "21") (name "GPIO19") (class "Default")
      (node (ref "J19") (pin "1") (pinfunction "1_1") (pintype "passive"))
    )
    (net (code "22") (name "GPIO20") (class "Default")
      (node (ref "J20") (pin "1") (pinfunction "1_1") (pintype "passive"))
    )
    (net (code "23") (name "GPIO21") (class "Default")
      (node (ref "J21") (pin "1") (pinfunction "1_1") (pintype "passive"))
    )
    (net (code "24") (name "GPIO22") (class "Default")
      (node (ref "J22") (pin "1") (pinfunction "1_1") (pintype "passive"))
    )
    (net (code "25") (name "GPIO23") (class "Default")
      (node (ref "J23") (pin "1") (pinfunction "1_1") (pintype "passive"))
    )
    (net (code "26") (name "GPIO24") (class "Default")
      (node (ref "J24") (pin "1") (pinfunction "1_1") (pintype "passive"))
    )
    (net (code "27") (name "GPIO25") (class "Default")
      (node (ref "J25") (pin "1") (pinfunction "1_1") (pintype "passive"))
    )
    (net (code "28") (name "SCL") (class "Default")
      (node (ref "PAD10") (pin "1") (pinfunction "P_1") (pintype "passive"))
      (node (ref "PAD14") (pin "1") (pinfunction "P_1") (pintype "passive"))
      (node (ref "PAD18") (pin "1") (pinfunction "P_1") (pintype "passive"))
      (node (ref "PAD2") (pin "1") (pinfunction "P_1") (pintype "passive"))
      (node (ref "PAD22") (pin "1") (pinfunction "P_1") (pintype "passive"))
      (node (ref "PAD26") (pin "1") (pinfunction "P_1") (pintype "passive"))
      (node (ref "PAD30") (pin "1") (pinfunction "P_1") (pintype "passive"))
      (node (ref "PAD34") (pin "1") (pinfunction "P_1") (pintype "passive"))
      (node (ref "PAD38") (pin "1") (pinfunction "P_1") (pintype "passive"))
      (node (ref "PAD42") (pin "1") (pinfunction "P_1") (pintype "passive"))
      (node (ref "PAD46") (pin "1") (pinfunction "P_1") (pintype "passive"))
      (node (ref "PAD50") (pin "1") (pinfunction "P_1") (pintype "passive"))
      (node (ref "PAD54") (pin "1") (pinfunction "P_1") (pintype "passive"))
      (node (ref "PAD58") (pin "1") (pinfunction "P_1") (pintype "passive"))
      (node (ref "PAD6") (pin "1") (pinfunction "P_1") (pintype "passive"))
      (node (ref "PAD62") (pin "1") (pinfunction "P_1") (pintype "passive"))
      (node (ref "PAD66") (pin "1") (pinfunction "P_1") (pintype "passive"))
      (node (ref "PAD70") (pin "1") (pinfunction "P_1") (pintype "passive"))
      (node (ref "PAD74") (pin "1") (pinfunction "P_1") (pintype "passive"))
      (node (ref "PAD78") (pin "1") (pinfunction "P_1") (pintype "passive"))
      (node (ref "PAD82") (pin "1") (pinfunction "P_1") (pintype "passive"))
      (node (ref "PAD86") (pin "1") (pinfunction "P_1") (pintype "passive"))
      (node (ref "PAD90") (pin "1") (pinfunction "P_1") (pintype "passive"))
      (node (ref "PAD94") (pin "1") (pinfunction "P_1") (pintype "passive"))
      (node (ref "PAD98") (pin "1") (pinfunction "P_1") (pintype "passive"))
      (node (ref "SCL") (pin "1") (pinfunction "P_1") (pintype "passive"))
      (node (ref "SCL1") (pin "1") (pinfunction "P_1") (pintype "passive"))
      (node (ref "SCL10") (pin "1") (pinfunction "P_1") (pintype "passive"))
      (node (ref "SCL11") (pin "1") (pinfunction "P_1") (pintype "passive"))
      (node (ref "SCL12") (pin "1") (pinfunction "P_1") (pintype "passive"))
      (node (ref "SCL13") (pin "1") (pinfunction "P_1") (pintype "passive"))
      (node (ref "SCL14") (pin "1") (pinfunction "P_1") (pintype "passive"))
      (node (ref "SCL15") (pin "1") (pinfunction "P_1") (pintype "passive"))
      (node (ref "SCL16") (pin "1") (pinfunction "P_1") (pintype "passive"))
      (node (ref "SCL17") (pin "1") (pinfunction "P_1") (pintype "passive"))
      (node (ref "SCL18") (pin "1") (pinfunction "P_1") (pintype "passive"))
      (node (ref "SCL19") (pin "1") (pinfunction "P_1") (pintype "passive"))
      (node (ref "SCL2") (pin "1") (pinfunction "P_1") (pintype "passive"))
      (node (ref "SCL20") (pin "1") (pinfunction "P_1") (pintype "passive"))
      (node (ref "SCL21") (pin "1") (pinfunction "P_1") (pintype "passive"))
      (node (ref "SCL22") (pin "1") (pinfunction "P_1") (pintype "passive"))
      (node (ref "SCL23") (pin "1") (pinfunction "P_1") (pintype "passive"))
      (node (ref "SCL24") (pin "1") (pinfunction "P_1") (pintype "passive"))
      (node (ref "SCL3") (pin "1") (pinfunction "P_1") (pintype "passive"))
      (node (ref "SCL4") (pin "1") (pinfunction "P_1") (pintype "passive"))
      (node (ref "SCL5") (pin "1") (pinfunction "P_1") (pintype "passive"))
      (node (ref "SCL6") (pin "1") (pinfunction "P_1") (pintype "passive"))
      (node (ref "SCL7") (pin "1") (pinfunction "P_1") (pintype "passive"))
      (node (ref "SCL8") (pin "1") (pinfunction "P_1") (pintype "passive"))
      (node (ref "SCL9") (pin "1") (pinfunction "P_1") (pintype "passive"))
    )
    (net (code "29") (name "SDA") (class "Default")
      (node (ref "PAD100") (pin "1") (pinfunction "P_1") (pintype "passive"))
      (node (ref "PAD12") (pin "1") (pinfunction "P_1") (pintype "passive"))
      (node (ref "PAD16") (pin "1") (pinfunction "P_1") (pintype "passive"))
      (node (ref "PAD20") (pin "1") (pinfunction "P_1") (pintype "passive"))
      (node (ref "PAD24") (pin "1") (pinfunction "P_1") (pintype "passive"))
      (node (ref "PAD28") (pin "1") (pinfunction "P_1") (pintype "passive"))
      (node (ref "PAD32") (pin "1") (pinfunction "P_1") (pintype "passive"))
      (node (ref "PAD36") (pin "1") (pinfunction "P_1") (pintype "passive"))
      (node (ref "PAD4") (pin "1") (pinfunction "P_1") (pintype "passive"))
      (node (ref "PAD40") (pin "1") (pinfunction "P_1") (pintype "passive"))
      (node (ref "PAD44") (pin "1") (pinfunction "P_1") (pintype "passive"))
      (node (ref "PAD48") (pin "1") (pinfunction "P_1") (pintype "passive"))
      (node (ref "PAD52") (pin "1") (pinfunction "P_1") (pintype "passive"))
      (node (ref "PAD56") (pin "1") (pinfunction "P_1") (pintype "passive"))
      (node (ref "PAD60") (pin "1") (pinfunction "P_1") (pintype "passive"))
      (node (ref "PAD64") (pin "1") (pinfunction "P_1") (pintype "passive"))
      (node (ref "PAD68") (pin "1") (pinfunction "P_1") (pintype "passive"))
      (node (ref "PAD72") (pin "1") (pinfunction "P_1") (pintype "passive"))
      (node (ref "PAD76") (pin "1") (pinfunction "P_1") (pintype "passive"))
      (node (ref "PAD8") (pin "1") (pinfunction "P_1") (pintype "passive"))
      (node (ref "PAD80") (pin "1") (pinfunction "P_1") (pintype "passive"))
      (node (ref "PAD84") (pin "1") (pinfunction "P_1") (pintype "passive"))
      (node (ref "PAD88") (pin "1") (pinfunction "P_1") (pintype "passive"))
      (node (ref "PAD92") (pin "1") (pinfunction "P_1") (pintype "passive"))
      (node (ref "PAD96") (pin "1") (pinfunction "P_1") (pintype "passive"))
      (node (ref "SDA") (pin "1") (pinfunction "P_1") (pintype "passive"))
      (node (ref "SDA1") (pin "1") (pinfunction "P_1") (pintype "passive"))
      (node (ref "SDA10") (pin "1") (pinfunction "P_1") (pintype "passive"))
      (node (ref "SDA11") (pin "1") (pinfunction "P_1") (pintype "passive"))
      (node (ref "SDA12") (pin "1") (pinfunction "P_1") (pintype "passive"))
      (node (ref "SDA13") (pin "1") (pinfunction "P_1") (pintype "passive"))
      (node (ref "SDA14") (pin "1") (pinfunction "P_1") (pintype "passive"))
      (node (ref "SDA15") (pin "1") (pinfunction "P_1") (pintype "passive"))
      (node (ref "SDA16") (pin "1") (pinfunction "P_1") (pintype "passive"))
      (node (ref "SDA17") (pin "1") (pinfunction "P_1") (pintype "passive"))
      (node (ref "SDA18") (pin "1") (pinfunction "P_1") (pintype "passive"))
      (node (ref "SDA19") (pin "1") (pinfunction "P_1") (pintype "passive"))
      (node (ref "SDA2") (pin "1") (pinfunction "P_1") (pintype "passive"))
      (node (ref "SDA20") (pin "1") (pinfunction "P_1") (pintype "passive"))
      (node (ref "SDA21") (pin "1") (pinfunction "P_1") (pintype "passive"))
      (node (ref "SDA22") (pin "1") (pinfunction "P_1") (pintype "passive"))
      (node (ref "SDA23") (pin "1") (pinfunction "P_1") (pintype "passive"))
      (node (ref "SDA24") (pin "1") (pinfunction "P_1") (pintype "passive"))
      (node (ref "SDA3") (pin "1") (pinfunction "P_1") (pintype "passive"))
      (node (ref "SDA4") (pin "1") (pinfunction "P_1") (pintype "passive"))
      (node (ref "SDA5") (pin "1") (pinfunction "P_1") (pintype "passive"))
      (node (ref "SDA6") (pin "1") (pinfunction "P_1") (pintype "passive"))
      (node (ref "SDA7") (pin "1") (pinfunction "P_1") (pintype "passive"))
      (node (ref "SDA8") (pin "1") (pinfunction "P_1") (pintype "passive"))
      (node (ref "SDA9") (pin "1") (pinfunction "P_1") (pintype "passive"))
    )
    (net (code "30") (name "VCC") (class "Default")
      (node (ref "PAD1") (pin "1") (pinfunction "P_1") (pintype "passive"))
      (node (ref "PAD13") (pin "1") (pinfunction "P_1") (pintype "passive"))
      (node (ref "PAD17") (pin "1") (pinfunction "P_1") (pintype "passive"))
      (node (ref "PAD21") (pin "1") (pinfunction "P_1") (pintype "passive"))
      (node (ref "PAD25") (pin "1") (pinfunction "P_1") (pintype "passive"))
      (node (ref "PAD29") (pin "1") (pinfunction "P_1") (pintype "passive"))
      (node (ref "PAD33") (pin "1") (pinfunction "P_1") (pintype "passive"))
      (node (ref "PAD37") (pin "1") (pinfunction "P_1") (pintype "passive"))
      (node (ref "PAD41") (pin "1") (pinfunction "P_1") (pintype "passive"))
      (node (ref "PAD45") (pin "1") (pinfunction "P_1") (pintype "passive"))
      (node (ref "PAD49") (pin "1") (pinfunction "P_1") (pintype "passive"))
      (node (ref "PAD5") (pin "1") (pinfunction "P_1") (pintype "passive"))
      (node (ref "PAD53") (pin "1") (pinfunction "P_1") (pintype "passive"))
      (node (ref "PAD57") (pin "1") (pinfunction "P_1") (pintype "passive"))
      (node (ref "PAD61") (pin "1") (pinfunction "P_1") (pintype "passive"))
      (node (ref "PAD65") (pin "1") (pinfunction "P_1") (pintype "passive"))
      (node (ref "PAD69") (pin "1") (pinfunction "P_1") (pintype "passive"))
      (node (ref "PAD73") (pin "1") (pinfunction "P_1") (pintype "passive"))
      (node (ref "PAD77") (pin "1") (pinfunction "P_1") (pintype "passive"))
      (node (ref "PAD81") (pin "1") (pinfunction "P_1") (pintype "passive"))
      (node (ref "PAD85") (pin "1") (pinfunction "P_1") (pintype "passive"))
      (node (ref "PAD89") (pin "1") (pinfunction "P_1") (pintype "passive"))
      (node (ref "PAD9") (pin "1") (pinfunction "P_1") (pintype "passive"))
      (node (ref "PAD93") (pin "1") (pinfunction "P_1") (pintype "passive"))
      (node (ref "PAD97") (pin "1") (pinfunction "P_1") (pintype "passive"))
      (node (ref "VCC") (pin "1") (pinfunction "P_1") (pintype "passive"))
      (node (ref "VCC1") (pin "1") (pinfunction "P_1") (pintype "passive"))
      (node (ref "VCC10") (pin "1") (pinfunction "P_1") (pintype "passive"))
      (node (ref "VCC11") (pin "1") (pinfunction "P_1") (pintype "passive"))
      (node (ref "VCC12") (pin "1") (pinfunction "P_1") (pintype "passive"))
      (node (ref "VCC13") (pin "1") (pinfunction "P_1") (pintype "passive"))
      (node (ref "VCC14") (pin "1") (pinfunction "P_1") (pintype "passive"))
      (node (ref "VCC15") (pin "1") (pinfunction "P_1") (pintype "passive"))
      (node (ref "VCC16") (pin "1") (pinfunction "P_1") (pintype "passive"))
      (node (ref "VCC17") (pin "1") (pinfunction "P_1") (pintype "passive"))
      (node (ref "VCC18") (pin "1") (pinfunction "P_1") (pintype "passive"))
      (node (ref "VCC19") (pin "1") (pinfunction "P_1") (pintype "passive"))
      (node (ref "VCC2") (pin "1") (pinfunction "P_1") (pintype "passive"))
      (node (ref "VCC20") (pin "1") (pinfunction "P_1") (pintype "passive"))
      (node (ref "VCC21") (pin "1") (pinfunction "P_1") (pintype "passive"))
      (node (ref "VCC22") (pin "1") (pinfunction "P_1") (pintype "passive"))
      (node (ref "VCC23") (pin "1") (pinfunction "P_1") (pintype "passive"))
      (node (ref "VCC24") (pin "1") (pinfunction "P_1") (pintype "passive"))
      (node (ref "VCC3") (pin "1") (pinfunction "P_1") (pintype "passive"))
      (node (ref "VCC4") (pin "1") (pinfunction "P_1") (pintype "passive"))
      (node (ref "VCC5") (pin "1") (pinfunction "P_1") (pintype "passive"))
      (node (ref "VCC6") (pin "1") (pinfunction "P_1") (pintype "passive"))
      (node (ref "VCC7") (pin "1") (pinfunction "P_1") (pintype "passive"))
      (node (ref "VCC8") (pin "1") (pinfunction "P_1") (pintype "passive"))
      (node (ref "VCC9") (pin "1") (pinfunction "P_1") (pintype "passive"))
    )
    (net (code "31") (name "unconnected-(J26-Pad1)") (class "Default")
      (node (ref "J26") (pin "1") (pinfunction "1_1") (pintype "passive"))
    )
    (net (code "32") (name "unconnected-(J26-Pad2)") (class "Default")
      (node (ref "J26") (pin "2") (pinfunction "2_2") (pintype "passive"))
    )
    (net (code "33") (name "unconnected-(J26-Pad3)") (class "Default")
      (node (ref "J26") (pin "3") (pinfunction "3_3") (pintype "passive"))
    )
    (net (code "34") (name "unconnected-(J26-Pad4)") (class "Default")
      (node (ref "J26") (pin "4") (pinfunction "4_4") (pintype "passive"))
    )
    (net (code "35") (name "unconnected-(J26-Pad5)") (class "Default")
      (node (ref "J26") (pin "5") (pinfunction "5_5") (pintype "passive"))
    )
    (net (code "36") (name "unconnected-(J26-Pad6)") (class "Default")
      (node (ref "J26") (pin "6") (pinfunction "6_6") (pintype "passive"))
    )
    (net (code "37") (name "unconnected-(J26-Pad7)") (class "Default")
      (node (ref "J26") (pin "7") (pinfunction "7_7") (pintype "passive"))
    )
    (net (code "38") (name "unconnected-(J26-Pad8)") (class "Default")
      (node (ref "J26") (pin "8") (pinfunction "8_8") (pintype "passive"))
    )
    (net (code "39") (name "unconnected-(J26-Pad9)") (class "Default")
      (node (ref "J26") (pin "9") (pinfunction "9_9") (pintype "passive"))
    )
    (net (code "40") (name "unconnected-(J26-Pad10)") (class "Default")
      (node (ref "J26") (pin "10") (pinfunction "10_10") (pintype "passive"))
    )
    (net (code "41") (name "unconnected-(J26-Pad11)") (class "Default")
      (node (ref "J26") (pin "11") (pinfunction "11_11") (pintype "passive"))
    )
    (net (code "42") (name "unconnected-(J26-Pad12)") (class "Default")
      (node (ref "J26") (pin "12") (pinfunction "12_12") (pintype "passive"))
    )
    (net (code "43") (name "unconnected-(J26-Pad13)") (class "Default")
      (node (ref "J26") (pin "13") (pinfunction "13_13") (pintype "passive"))
    )
    (net (code "44") (name "unconnected-(J26-Pad14)") (class "Default")
      (node (ref "J26") (pin "14") (pinfunction "14_14") (pintype "passive"))
    )
    (net (code "45") (name "unconnected-(J26-Pad15)") (class "Default")
      (node (ref "J26") (pin "15") (pinfunction "15_15") (pintype "passive"))
    )
    (net (code "46") (name "unconnected-(J27-Pad1)") (class "Default")
      (node (ref "J27") (pin "1") (pinfunction "1_1") (pintype "passive"))
    )
    (net (code "47") (name "unconnected-(J27-Pad2)") (class "Default")
      (node (ref "J27") (pin "2") (pinfunction "2_2") (pintype "passive"))
    )
    (net (code "48") (name "unconnected-(J27-Pad3)") (class "Default")
      (node (ref "J27") (pin "3") (pinfunction "3_3") (pintype "passive"))
    )
    (net (code "49") (name "unconnected-(J27-Pad4)") (class "Default")
      (node (ref "J27") (pin "4") (pinfunction "4_4") (pintype "passive"))
    )
    (net (code "50") (name "unconnected-(J27-Pad5)") (class "Default")
      (node (ref "J27") (pin "5") (pinfunction "5_5") (pintype "passive"))
    )
    (net (code "51") (name "unconnected-(J27-Pad6)") (class "Default")
      (node (ref "J27") (pin "6") (pinfunction "6_6") (pintype "passive"))
    )
    (net (code "52") (name "unconnected-(J27-Pad7)") (class "Default")
      (node (ref "J27") (pin "7") (pinfunction "7_7") (pintype "passive"))
    )
    (net (code "53") (name "unconnected-(J27-Pad8)") (class "Default")
      (node (ref "J27") (pin "8") (pinfunction "8_8") (pintype "passive"))
    )
    (net (code "54") (name "unconnected-(J27-Pad9)") (class "Default")
      (node (ref "J27") (pin "9") (pinfunction "9_9") (pintype "passive"))
    )
    (net (code "55") (name "unconnected-(J27-Pad10)") (class "Default")
      (node (ref "J27") (pin "10") (pinfunction "10_10") (pintype "passive"))
    )
    (net (code "56") (name "unconnected-(J27-Pad11)") (class "Default")
      (node (ref "J27") (pin "11") (pinfunction "11_11") (pintype "passive"))
    )
    (net (code "57") (name "unconnected-(J27-Pad12)") (class "Default")
      (node (ref "J27") (pin "12") (pinfunction "12_12") (pintype "passive"))
    )
    (net (code "58") (name "unconnected-(J27-Pad13)") (class "Default")
      (node (ref "J27") (pin "13") (pinfunction "13_13") (pintype "passive"))
    )
    (net (code "59") (name "unconnected-(J27-Pad14)") (class "Default")
      (node (ref "J27") (pin "14") (pinfunction "14_14") (pintype "passive"))
    )
    (net (code "60") (name "unconnected-(J27-Pad15)") (class "Default")
      (node (ref "J27") (pin "15") (pinfunction "15_15") (pintype "passive"))
    )
  )
)
